# recv_board.net
KiCad netlist of a schematic drawn in Altium Designer
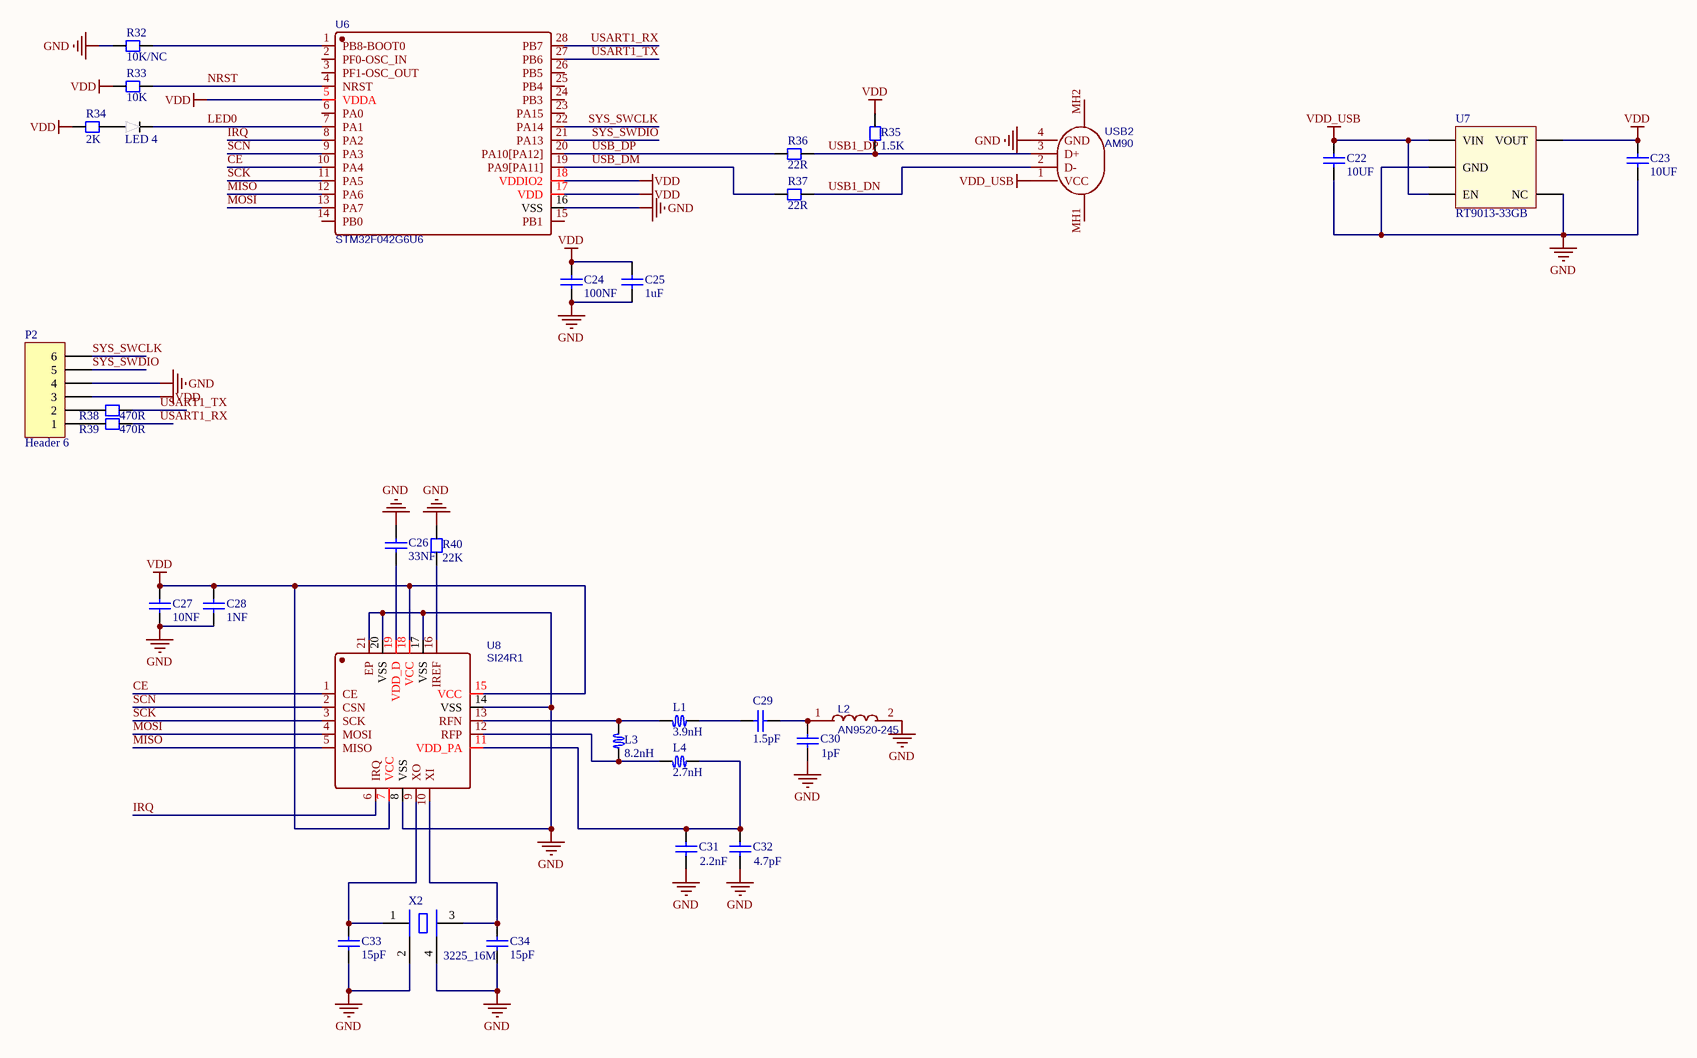
[diagram p0: recv_board.SchDoc]

(export (version "E")
  (design (tool "Eeschema 10.0.6"))
  (components
    (comp (ref "C22")
      (value "10UF")
      (footprint "CC1608-0603")
      (description "0603封装的电容")
      (fields (field (name "PUBLISHER") "Altium Limited"))
      (libsource (lib "base") (part "Cap Chip 0603"))
    )
    (comp (ref "C23")
      (value "10UF")
      (footprint "CC1608-0603")
      (description "0603封装的电容")
      (fields (field (name "PUBLISHER") "Altium Limited"))
      (libsource (lib "base") (part "Cap Chip 0603"))
    )
    (comp (ref "C24")
      (value "100NF")
      (footprint "CC1608-0603")
      (description "0603封装的电容")
      (fields (field (name "PUBLISHER") "Altium Limited"))
      (libsource (lib "base") (part "Cap Chip 0603"))
    )
    (comp (ref "C25")
      (value "1uF")
      (footprint "CC1608-0603")
      (description "0603封装的电容")
      (fields (field (name "PUBLISHER") "Altium Limited"))
      (libsource (lib "base") (part "Cap Chip 0603"))
    )
    (comp (ref "C26")
      (value "33NF")
      (footprint "CC1608-0603")
      (description "0603封装的电容")
      (fields (field (name "PUBLISHER") "Altium Limited"))
      (libsource (lib "base") (part "Cap Chip 0603"))
    )
    (comp (ref "C27")
      (value "10NF")
      (footprint "CC1608-0603")
      (description "0603封装的电容")
      (fields (field (name "PUBLISHER") "Altium Limited"))
      (libsource (lib "base") (part "Cap Chip 0603"))
    )
    (comp (ref "C28")
      (value "1NF")
      (footprint "CC1608-0603")
      (description "0603封装的电容")
      (fields (field (name "PUBLISHER") "Altium Limited"))
      (libsource (lib "base") (part "Cap Chip 0603"))
    )
    (comp (ref "C29")
      (value "1.5pF")
      (footprint "CC1608-0603")
      (description "0603封装的电容")
      (fields (field (name "PUBLISHER") "Altium Limited"))
      (libsource (lib "base") (part "Cap Chip 0603"))
    )
    (comp (ref "C30")
      (value "1pF")
      (footprint "CC1608-0603")
      (description "0603封装的电容")
      (fields (field (name "PUBLISHER") "Altium Limited"))
      (libsource (lib "base") (part "Cap Chip 0603"))
    )
    (comp (ref "C31")
      (value "2.2nF")
      (footprint "CC1608-0603")
      (description "0603封装的电容")
      (fields (field (name "PUBLISHER") "Altium Limited"))
      (libsource (lib "base") (part "Cap Chip 0603"))
    )
    (comp (ref "C32")
      (value "4.7pF")
      (footprint "CC1608-0603")
      (description "0603封装的电容")
      (fields (field (name "PUBLISHER") "Altium Limited"))
      (libsource (lib "base") (part "Cap Chip 0603"))
    )
    (comp (ref "C33")
      (value "15pF")
      (footprint "CC1608-0603")
      (description "0603封装的电容")
      (fields (field (name "PUBLISHER") "Altium Limited"))
      (libsource (lib "base") (part "Cap Chip 0603"))
    )
    (comp (ref "C34")
      (value "15pF")
      (footprint "CC1608-0603")
      (description "0603封装的电容")
      (fields (field (name "PUBLISHER") "Altium Limited"))
      (libsource (lib "base") (part "Cap Chip 0603"))
    )
    (comp (ref "L1")
      (value "3.9nH")
      (footprint "Inductor-0603")
      (description "贴片电感 0603封装")
      (libsource (lib "base") (part "Inductor-0603"))
    )
    (comp (ref "L2")
      (value "AN9520-245")
      (footprint "ANT-SMD_L9.5-W2.1")
      (fields (field (name "MANUFACTURER") "rainsun(霖昱微)"))
      (libsource (lib "antenna") (part "AN9520-245"))
    )
    (comp (ref "L3")
      (value "8.2nH")
      (footprint "Inductor-0603")
      (description "贴片电感 0603封装")
      (libsource (lib "") (part "Inductor-0603_1"))
    )
    (comp (ref "L4")
      (value "2.7nH")
      (footprint "Inductor-0603")
      (description "贴片电感 0603封装")
      (libsource (lib "base") (part "Inductor-0603"))
    )
    (comp (ref "LED 4") (value "LED 0603") (footprint "LED 0603") (libsource (lib "base") (part "LED 0603")))
    (comp (ref "P2")
      (value "Header 6")
      (footprint "HDR1X6")
      (description "Header, 6-Pin")
      (fields (field (name "PUBLISHER") "Altium Limited"))
      (libsource (lib "Connectors") (part "Header 6"))
    )
    (comp (ref "R32")
      (value "10K/NC")
      (footprint "CR1608-0603")
      (description "0603封装电阻")
      (fields (field (name "PUBLISHER") "Altium Limited"))
      (libsource (lib "base") (part "Resistor Chip 0603"))
    )
    (comp (ref "R33")
      (value "10K")
      (footprint "CR1608-0603")
      (description "0603封装电阻")
      (fields (field (name "PUBLISHER") "Altium Limited"))
      (libsource (lib "") (part "Resistor Chip 0603_1"))
    )
    (comp (ref "R34")
      (value "2K")
      (footprint "CR1608-0603")
      (description "0603封装电阻")
      (fields (field (name "PUBLISHER") "Altium Limited"))
      (libsource (lib "") (part "Resistor Chip 0603_1"))
    )
    (comp (ref "R35")
      (value "1.5K")
      (footprint "CR1608-0603")
      (description "0603封装电阻")
      (fields (field (name "PUBLISHER") "Altium Limited"))
      (libsource (lib "") (part "Resistor Chip 0603_2"))
    )
    (comp (ref "R36")
      (value "22R")
      (footprint "CR1608-0603")
      (description "0603封装电阻")
      (fields (field (name "PUBLISHER") "Altium Limited"))
      (libsource (lib "") (part "Resistor Chip 0603_1"))
    )
    (comp (ref "R37")
      (value "22R")
      (footprint "CR1608-0603")
      (description "0603封装电阻")
      (fields (field (name "PUBLISHER") "Altium Limited"))
      (libsource (lib "") (part "Resistor Chip 0603_1"))
    )
    (comp (ref "R38")
      (value "470R")
      (footprint "CR1608-0603")
      (description "贴片电阻")
      (libsource (lib "tianxiaohua_Schlib") (part "Chip resistor"))
    )
    (comp (ref "R39")
      (value "470R")
      (footprint "CR1608-0603")
      (description "贴片电阻")
      (libsource (lib "tianxiaohua_Schlib") (part "Chip resistor"))
    )
    (comp (ref "R40")
      (value "22K")
      (footprint "CR1608-0603")
      (description "0603封装电阻")
      (fields (field (name "PUBLISHER") "Altium Limited"))
      (libsource (lib "") (part "Resistor Chip 0603_2"))
    )
    (comp (ref "U6")
      (value "STM32F042G6U6")
      (footprint "UFQFPN-28")
      (fields (field (name "MANUFACTURER") "ST(意法半导体)") (field (name "CONTRIBUTOR") "LCSC"))
      (libsource (lib "singlechip") (part "STM32F042G6U6"))
    )
    (comp (ref "U7")
      (value "RT9013-33GB")
      (footprint "SOT23-5")
      (description "LDO 2.2-5.2V IN 500Ma OUT SOT23-5")
      (libsource (lib "power-chip") (part "RT9013-33GB"))
    )
    (comp (ref "U8")
      (value "SI24R1")
      (footprint "QFN-20")
      (fields (field (name "MANUFACTURER") "南京中科微") (field (name "MANUFACTURER PART") "Si24R1"))
      (libsource (lib "sensor") (part "SI24R1"))
    )
    (comp (ref "USB2")
      (value "AM90")
      (footprint "USB-AM")
      (fields (field (name "MANUFACTURER") "SHOU HAN(首韩)") (field (name "CONTRIBUTOR") "LCSC"))
      (libsource (lib "Connectors") (part "USB-AM90"))
    )
    (comp (ref "X2")
      (value "3225_16M")
      (footprint "XTAL-3225")
      (description "3225封装的晶振")
      (libsource (lib "base") (part "XTAL 3225"))
    )
  )
  (nets
    (net (code "1") (name "/CE") (class "Default")
      (node (ref "U6") (pin "10") (pinfunction "PA4_10") (pintype "passive"))
      (node (ref "U8") (pin "1") (pinfunction "CE_1") (pintype "passive"))
    )
    (net (code "2") (name "/IRQ") (class "Default")
      (node (ref "U6") (pin "8") (pinfunction "PA2_8") (pintype "passive"))
      (node (ref "U8") (pin "6") (pinfunction "IRQ_6") (pintype "passive"))
    )
    (net (code "3") (name "/LED0") (class "Default")
      (node (ref "LED 4") (pin "2") (pinfunction "2_2") (pintype "passive"))
      (node (ref "U6") (pin "7") (pinfunction "PA1_7") (pintype "passive"))
    )
    (net (code "4") (name "/MISO") (class "Default")
      (node (ref "U6") (pin "12") (pinfunction "PA6_12") (pintype "passive"))
      (node (ref "U8") (pin "5") (pinfunction "MISO_5") (pintype "passive"))
    )
    (net (code "5") (name "/MOSI") (class "Default")
      (node (ref "U6") (pin "13") (pinfunction "PA7_13") (pintype "passive"))
      (node (ref "U8") (pin "4") (pinfunction "MOSI_4") (pintype "passive"))
    )
    (net (code "6") (name "/NRST") (class "Default")
      (node (ref "R33") (pin "1") (pinfunction "1_1") (pintype "passive"))
      (node (ref "U6") (pin "4") (pinfunction "NRST_4") (pintype "passive"))
    )
    (net (code "7") (name "/SCK") (class "Default")
      (node (ref "U6") (pin "11") (pinfunction "PA5_11") (pintype "passive"))
      (node (ref "U8") (pin "3") (pinfunction "SCK_3") (pintype "passive"))
    )
    (net (code "8") (name "/SCN") (class "Default")
      (node (ref "U6") (pin "9") (pinfunction "PA3_9") (pintype "passive"))
      (node (ref "U8") (pin "2") (pinfunction "CSN_2") (pintype "passive"))
    )
    (net (code "9") (name "/SYS_SWCLK") (class "Default")
      (node (ref "P2") (pin "6") (pinfunction "6_6") (pintype "passive"))
      (node (ref "U6") (pin "22") (pinfunction "PA14_22") (pintype "passive"))
    )
    (net (code "10") (name "/SYS_SWDIO") (class "Default")
      (node (ref "P2") (pin "5") (pinfunction "5_5") (pintype "passive"))
      (node (ref "U6") (pin "21") (pinfunction "PA13_21") (pintype "passive"))
    )
    (net (code "11") (name "/USART1_RX") (class "Default")
      (node (ref "R39") (pin "1") (pinfunction "1_1") (pintype "passive"))
      (node (ref "U6") (pin "28") (pinfunction "PB7_28") (pintype "passive"))
    )
    (net (code "12") (name "/USART1_TX") (class "Default")
      (node (ref "R38") (pin "1") (pinfunction "1_1") (pintype "passive"))
      (node (ref "U6") (pin "27") (pinfunction "PB6_27") (pintype "passive"))
    )
    (net (code "13") (name "/USB1_DN") (class "Default")
      (node (ref "R37") (pin "1") (pinfunction "1_1") (pintype "passive"))
      (node (ref "USB2") (pin "2") (pinfunction "D-_2") (pintype "passive"))
    )
    (net (code "14") (name "/USB1_DP") (class "Default")
      (node (ref "R35") (pin "2") (pinfunction "2_2") (pintype "passive"))
      (node (ref "R36") (pin "1") (pinfunction "1_1") (pintype "passive"))
      (node (ref "USB2") (pin "3") (pinfunction "D+_3") (pintype "passive"))
    )
    (net (code "15") (name "/USB_DM") (class "Default")
      (node (ref "R37") (pin "2") (pinfunction "2_2") (pintype "passive"))
      (node (ref "U6") (pin "19") (pinfunction "PA9[PA11]_19") (pintype "passive"))
    )
    (net (code "16") (name "/USB_DP") (class "Default")
      (node (ref "R36") (pin "2") (pinfunction "2_2") (pintype "passive"))
      (node (ref "U6") (pin "20") (pinfunction "PA10[PA12]_20") (pintype "passive"))
    )
    (net (code "17") (name "GND") (class "Default")
      (node (ref "C22") (pin "1") (pinfunction "1_1") (pintype "passive"))
      (node (ref "C23") (pin "1") (pinfunction "1_1") (pintype "passive"))
      (node (ref "C24") (pin "1") (pinfunction "1_1") (pintype "passive"))
      (node (ref "C25") (pin "1") (pinfunction "1_1") (pintype "passive"))
      (node (ref "C26") (pin "2") (pinfunction "2_2") (pintype "passive"))
      (node (ref "C27") (pin "1") (pinfunction "1_1") (pintype "passive"))
      (node (ref "C28") (pin "1") (pinfunction "1_1") (pintype "passive"))
      (node (ref "C30") (pin "2") (pinfunction "2_2") (pintype "passive"))
      (node (ref "C31") (pin "2") (pinfunction "2_2") (pintype "passive"))
      (node (ref "C32") (pin "2") (pinfunction "2_2") (pintype "passive"))
      (node (ref "C33") (pin "1") (pinfunction "1_1") (pintype "passive"))
      (node (ref "C34") (pin "1") (pinfunction "1_1") (pintype "passive"))
      (node (ref "L2") (pin "2") (pinfunction "2_2") (pintype "passive"))
      (node (ref "P2") (pin "4") (pinfunction "4_4") (pintype "passive"))
      (node (ref "R32") (pin "1") (pinfunction "1_1") (pintype "passive"))
      (node (ref "R40") (pin "1") (pinfunction "1_1") (pintype "passive"))
      (node (ref "U6") (pin "16") (pinfunction "VSS_16") (pintype "passive"))
      (node (ref "U7") (pin "2") (pinfunction "GND_2") (pintype "passive"))
      (node (ref "U7") (pin "4") (pinfunction "NC_4") (pintype "passive"))
      (node (ref "U8") (pin "14") (pinfunction "VSS_14") (pintype "passive"))
      (node (ref "U8") (pin "17") (pinfunction "VSS_17") (pintype "passive"))
      (node (ref "U8") (pin "20") (pinfunction "VSS_20") (pintype "passive"))
      (node (ref "U8") (pin "21") (pinfunction "EP_21") (pintype "passive"))
      (node (ref "U8") (pin "8") (pinfunction "VSS_8") (pintype "passive"))
      (node (ref "USB2") (pin "4") (pinfunction "GND_4") (pintype "passive"))
      (node (ref "X2") (pin "2") (pinfunction "GND_2") (pintype "passive"))
      (node (ref "X2") (pin "4") (pinfunction "GND_4") (pintype "passive"))
    )
    (net (code "18") (name "Net-(C29-Pad1)") (class "Default")
      (node (ref "C29") (pin "1") (pinfunction "1_1") (pintype "passive"))
      (node (ref "C30") (pin "1") (pinfunction "1_1") (pintype "passive"))
      (node (ref "L2") (pin "1") (pinfunction "1_1") (pintype "passive"))
    )
    (net (code "19") (name "Net-(C29-Pad2)") (class "Default")
      (node (ref "C29") (pin "2") (pinfunction "2_2") (pintype "passive"))
      (node (ref "L1") (pin "1") (pinfunction "1_1") (pintype "passive"))
    )
    (net (code "20") (name "Net-(LED 4-Pad1)") (class "Default")
      (node (ref "LED 4") (pin "1") (pinfunction "1_1") (pintype "passive"))
      (node (ref "R34") (pin "1") (pinfunction "1_1") (pintype "passive"))
    )
    (net (code "21") (name "Net-(P2-Pad1)") (class "Default")
      (node (ref "P2") (pin "1") (pinfunction "1_1") (pintype "passive"))
      (node (ref "R39") (pin "2") (pinfunction "2_2") (pintype "passive"))
    )
    (net (code "22") (name "Net-(P2-Pad2)") (class "Default")
      (node (ref "P2") (pin "2") (pinfunction "2_2") (pintype "passive"))
      (node (ref "R38") (pin "2") (pinfunction "2_2") (pintype "passive"))
    )
    (net (code "23") (name "Net-(U6-PB8-BOOT0)") (class "Default")
      (node (ref "R32") (pin "2") (pinfunction "2_2") (pintype "passive"))
      (node (ref "U6") (pin "1") (pinfunction "PB8-BOOT0_1") (pintype "passive"))
    )
    (net (code "24") (name "Net-(U8-IREF)") (class "Default")
      (node (ref "R40") (pin "2") (pinfunction "2_2") (pintype "passive"))
      (node (ref "U8") (pin "16") (pinfunction "IREF_16") (pintype "passive"))
    )
    (net (code "25") (name "Net-(U8-RFN)") (class "Default")
      (node (ref "L1") (pin "2") (pinfunction "2_2") (pintype "passive"))
      (node (ref "L3") (pin "2") (pinfunction "2_2") (pintype "passive"))
      (node (ref "U8") (pin "13") (pinfunction "RFN_13") (pintype "passive"))
    )
    (net (code "26") (name "Net-(U8-RFP)") (class "Default")
      (node (ref "L3") (pin "1") (pinfunction "1_1") (pintype "passive"))
      (node (ref "L4") (pin "2") (pinfunction "2_2") (pintype "passive"))
      (node (ref "U8") (pin "12") (pinfunction "RFP_12") (pintype "passive"))
    )
    (net (code "27") (name "Net-(U8-VDD_D)") (class "Default")
      (node (ref "C26") (pin "1") (pinfunction "1_1") (pintype "passive"))
      (node (ref "U8") (pin "19") (pinfunction "VDD_D_19") (pintype "passive"))
    )
    (net (code "28") (name "Net-(U8-VDD_PA)") (class "Default")
      (node (ref "C31") (pin "1") (pinfunction "1_1") (pintype "passive"))
      (node (ref "C32") (pin "1") (pinfunction "1_1") (pintype "passive"))
      (node (ref "L4") (pin "1") (pinfunction "1_1") (pintype "passive"))
      (node (ref "U8") (pin "11") (pinfunction "VDD_PA_11") (pintype "passive"))
    )
    (net (code "29") (name "Net-(U8-XI)") (class "Default")
      (node (ref "C34") (pin "2") (pinfunction "2_2") (pintype "passive"))
      (node (ref "U8") (pin "10") (pinfunction "XI_10") (pintype "passive"))
      (node (ref "X2") (pin "3") (pinfunction "OSC2_3") (pintype "passive"))
    )
    (net (code "30") (name "Net-(U8-XO)") (class "Default")
      (node (ref "C33") (pin "2") (pinfunction "2_2") (pintype "passive"))
      (node (ref "U8") (pin "9") (pinfunction "XO_9") (pintype "passive"))
      (node (ref "X2") (pin "1") (pinfunction "OSC1_1") (pintype "passive"))
    )
    (net (code "31") (name "VDD") (class "Default")
      (node (ref "C23") (pin "2") (pinfunction "2_2") (pintype "passive"))
      (node (ref "C24") (pin "2") (pinfunction "2_2") (pintype "passive"))
      (node (ref "C25") (pin "2") (pinfunction "2_2") (pintype "passive"))
      (node (ref "C27") (pin "2") (pinfunction "2_2") (pintype "passive"))
      (node (ref "C28") (pin "2") (pinfunction "2_2") (pintype "passive"))
      (node (ref "P2") (pin "3") (pinfunction "3_3") (pintype "passive"))
      (node (ref "R33") (pin "2") (pinfunction "2_2") (pintype "passive"))
      (node (ref "R34") (pin "2") (pinfunction "2_2") (pintype "passive"))
      (node (ref "R35") (pin "1") (pinfunction "1_1") (pintype "passive"))
      (node (ref "U6") (pin "17") (pinfunction "VDD_17") (pintype "passive"))
      (node (ref "U6") (pin "18") (pinfunction "VDDIO2_18") (pintype "passive"))
      (node (ref "U6") (pin "5") (pinfunction "VDDA_5") (pintype "passive"))
      (node (ref "U7") (pin "5") (pinfunction "VOUT_5") (pintype "passive"))
      (node (ref "U8") (pin "15") (pinfunction "VCC_15") (pintype "passive"))
      (node (ref "U8") (pin "18") (pinfunction "VCC_18") (pintype "passive"))
      (node (ref "U8") (pin "7") (pinfunction "VCC_7") (pintype "passive"))
    )
    (net (code "32") (name "VDD_USB") (class "Default")
      (node (ref "C22") (pin "2") (pinfunction "2_2") (pintype "passive"))
      (node (ref "U7") (pin "1") (pinfunction "VIN_1") (pintype "passive"))
      (node (ref "U7") (pin "3") (pinfunction "EN_3") (pintype "passive"))
      (node (ref "USB2") (pin "1") (pinfunction "VCC_1") (pintype "passive"))
    )
    (net (code "33") (name "unconnected-(U6-PA0-Pad6)") (class "Default")
      (node (ref "U6") (pin "6") (pinfunction "PA0_6") (pintype "passive"))
    )
    (net (code "34") (name "unconnected-(U6-PA15-Pad23)") (class "Default")
      (node (ref "U6") (pin "23") (pinfunction "PA15_23") (pintype "passive"))
    )
    (net (code "35") (name "unconnected-(U6-PB0-Pad14)") (class "Default")
      (node (ref "U6") (pin "14") (pinfunction "PB0_14") (pintype "passive"))
    )
    (net (code "36") (name "unconnected-(U6-PB1-Pad15)") (class "Default")
      (node (ref "U6") (pin "15") (pinfunction "PB1_15") (pintype "passive"))
    )
    (net (code "37") (name "unconnected-(U6-PB3-Pad24)") (class "Default")
      (node (ref "U6") (pin "24") (pinfunction "PB3_24") (pintype "passive"))
    )
    (net (code "38") (name "unconnected-(U6-PB4-Pad25)") (class "Default")
      (node (ref "U6") (pin "25") (pinfunction "PB4_25") (pintype "passive"))
    )
    (net (code "39") (name "unconnected-(U6-PB5-Pad26)") (class "Default")
      (node (ref "U6") (pin "26") (pinfunction "PB5_26") (pintype "passive"))
    )
    (net (code "40") (name "unconnected-(U6-PF0-OSC_IN-Pad2)") (class "Default")
      (node (ref "U6") (pin "2") (pinfunction "PF0-OSC_IN_2") (pintype "passive"))
    )
    (net (code "41") (name "unconnected-(U6-PF1-OSC_OUT-Pad3)") (class "Default")
      (node (ref "U6") (pin "3") (pinfunction "PF1-OSC_OUT_3") (pintype "passive"))
    )
    (net (code "42") (name "unconnected-(USB2-PadMH1)") (class "Default")
      (node (ref "USB2") (pin "MH1") (pinfunction "MH1_MH1") (pintype "passive"))
    )
    (net (code "43") (name "unconnected-(USB2-PadMH2)") (class "Default")
      (node (ref "USB2") (pin "MH2") (pinfunction "MH2_MH2") (pintype "passive"))
    )
  )
)
